# motorcontrol.net
KiCad netlist of a schematic drawn in EAGLE
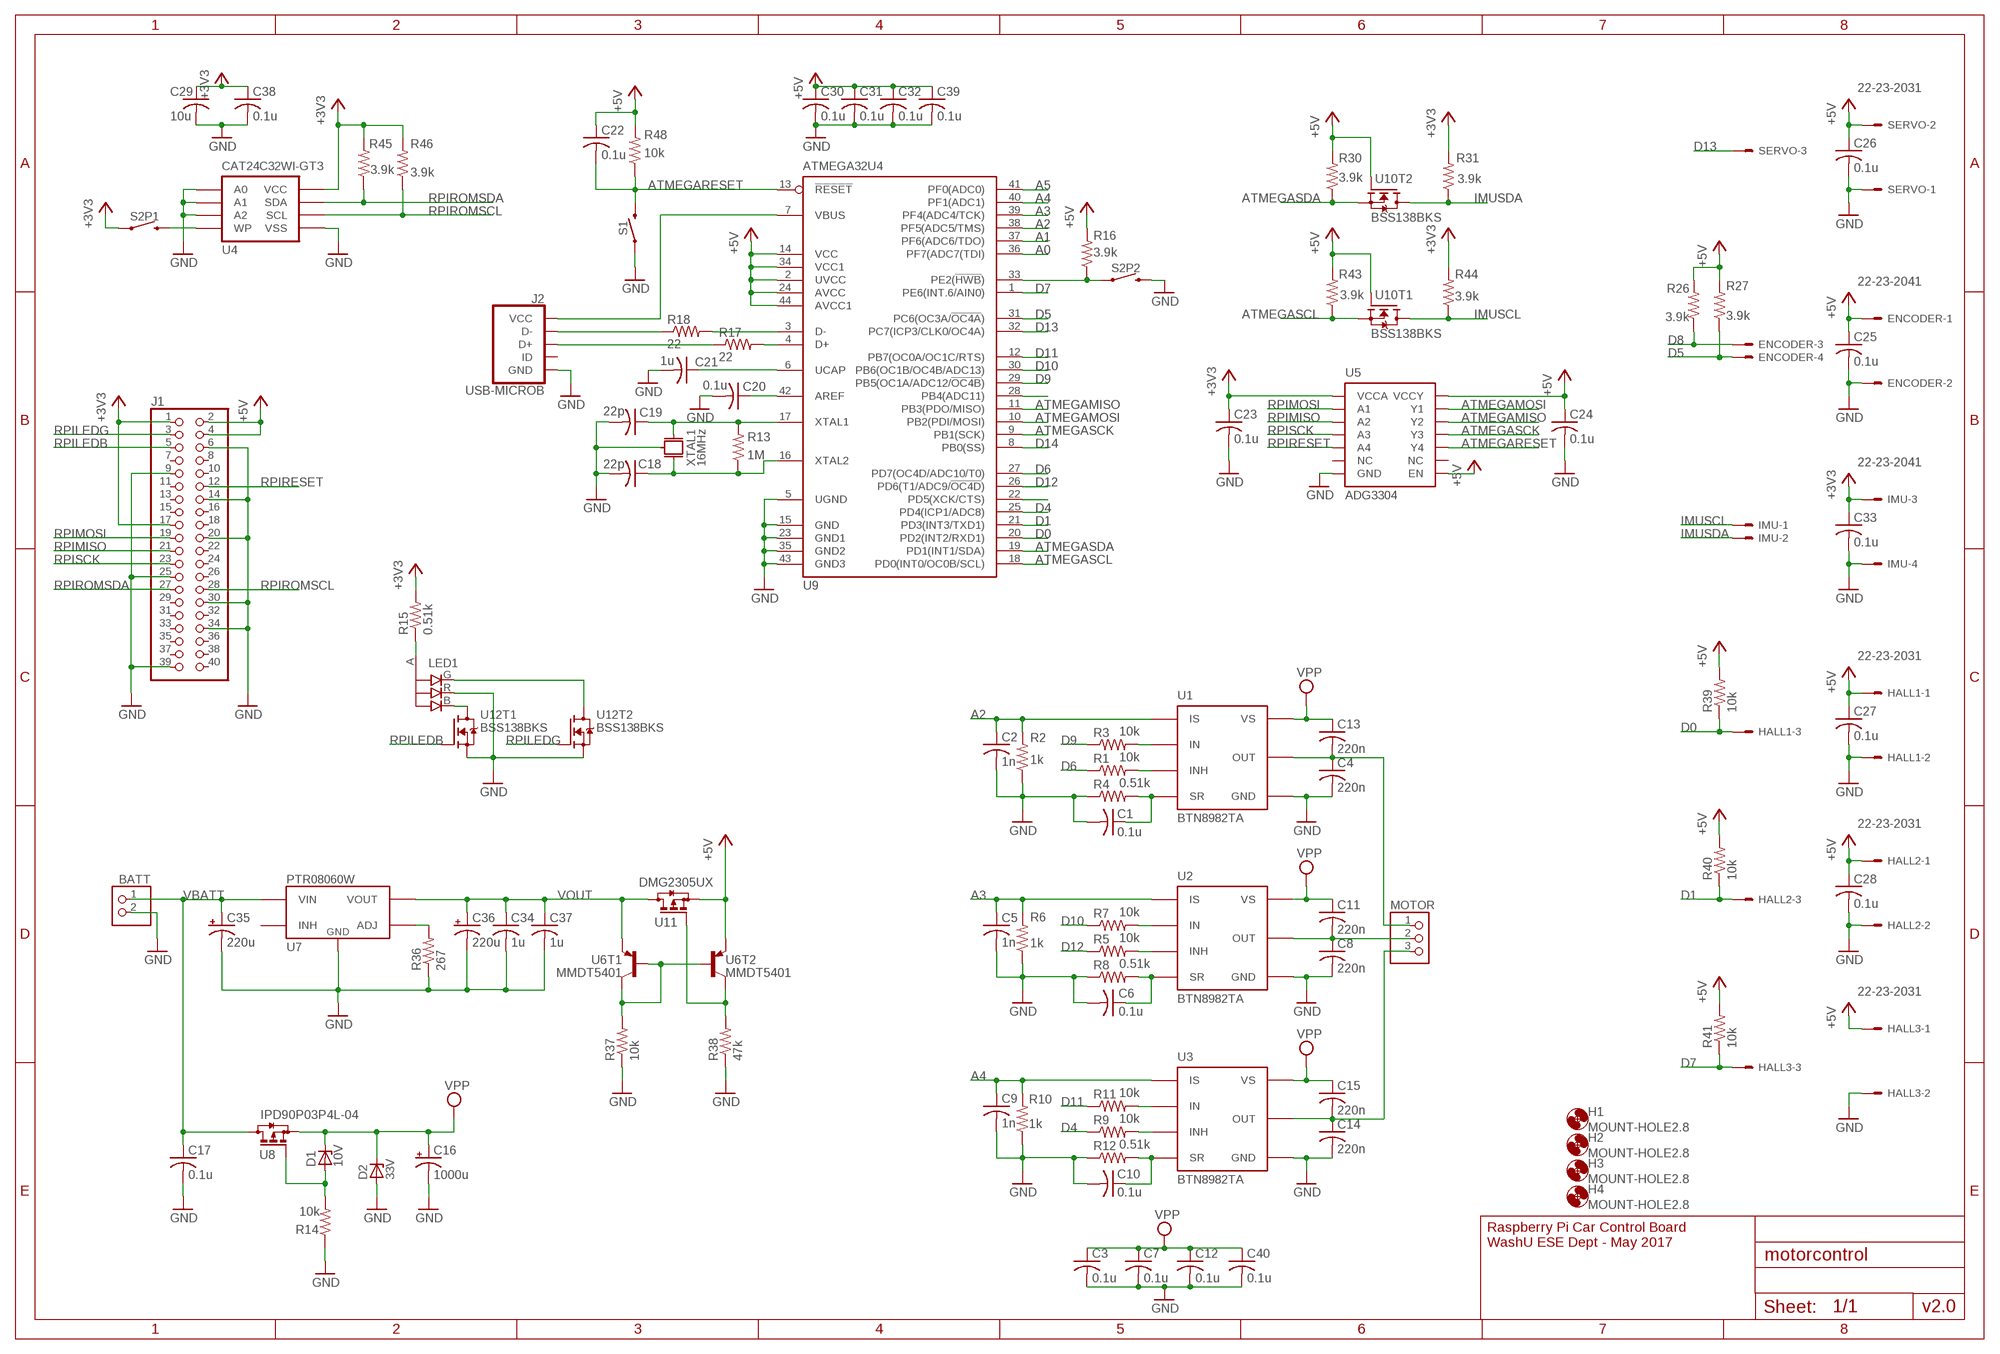
[diagram p0: schematic, sheet 1]

(export (version "E")
  (design (tool "Eeschema 10.0.6"))
  (components
    (comp (ref "BATT")
      (value "ULTRAFIT_2CIRCVCLIP")
      (footprint "eagle-import:ULTRAFIT_2CIRC_VERTCLIP")
      (libsource (lib "eagle-import") (part "ULTRAFIT_2CIRCVCLIP"))
    )
    (comp (ref "C1")
      (value "0.1u")
      (footprint "eagle-import:C1206")
      (libsource (lib "eagle-import") (part "C-USC1206"))
    )
    (comp (ref "C2")
      (value "1n")
      (footprint "eagle-import:C1206")
      (libsource (lib "eagle-import") (part "C-USC1206"))
    )
    (comp (ref "C3")
      (value "0.1u")
      (footprint "eagle-import:C1206")
      (libsource (lib "eagle-import") (part "C-USC1206"))
    )
    (comp (ref "C4")
      (value "220n")
      (footprint "eagle-import:C1206")
      (libsource (lib "eagle-import") (part "C-USC1206"))
    )
    (comp (ref "C5")
      (value "1n")
      (footprint "eagle-import:C1206")
      (libsource (lib "eagle-import") (part "C-USC1206"))
    )
    (comp (ref "C6")
      (value "0.1u")
      (footprint "eagle-import:C1206")
      (libsource (lib "eagle-import") (part "C-USC1206"))
    )
    (comp (ref "C7")
      (value "0.1u")
      (footprint "eagle-import:C1206")
      (libsource (lib "eagle-import") (part "C-USC1206"))
    )
    (comp (ref "C8")
      (value "220n")
      (footprint "eagle-import:C1206")
      (libsource (lib "eagle-import") (part "C-USC1206"))
    )
    (comp (ref "C9")
      (value "1n")
      (footprint "eagle-import:C1206")
      (libsource (lib "eagle-import") (part "C-USC1206"))
    )
    (comp (ref "C10")
      (value "0.1u")
      (footprint "eagle-import:C1206")
      (libsource (lib "eagle-import") (part "C-USC1206"))
    )
    (comp (ref "C11")
      (value "220n")
      (footprint "eagle-import:C1206")
      (libsource (lib "eagle-import") (part "C-USC1206"))
    )
    (comp (ref "C12")
      (value "0.1u")
      (footprint "eagle-import:C1206")
      (libsource (lib "eagle-import") (part "C-USC1206"))
    )
    (comp (ref "C13")
      (value "220n")
      (footprint "eagle-import:C1206")
      (libsource (lib "eagle-import") (part "C-USC1206"))
    )
    (comp (ref "C14")
      (value "220n")
      (footprint "eagle-import:C1206")
      (libsource (lib "eagle-import") (part "C-USC1206"))
    )
    (comp (ref "C15")
      (value "220n")
      (footprint "eagle-import:C1206")
      (libsource (lib "eagle-import") (part "C-USC1206"))
    )
    (comp (ref "C16")
      (value "1000u")
      (footprint "eagle-import:E5-10,5")
      (libsource (lib "eagle-import") (part "CPOL-USE5-10.5"))
    )
    (comp (ref "C17")
      (value "0.1u")
      (footprint "eagle-import:C1206")
      (libsource (lib "eagle-import") (part "C-USC1206"))
    )
    (comp (ref "C18")
      (value "22p")
      (footprint "eagle-import:C1206")
      (libsource (lib "eagle-import") (part "C-USC1206"))
    )
    (comp (ref "C19")
      (value "22p")
      (footprint "eagle-import:C1206")
      (libsource (lib "eagle-import") (part "C-USC1206"))
    )
    (comp (ref "C20")
      (value "0.1u")
      (footprint "eagle-import:C1206")
      (libsource (lib "eagle-import") (part "C-USC1206"))
    )
    (comp (ref "C21")
      (value "1u")
      (footprint "eagle-import:C1206")
      (libsource (lib "eagle-import") (part "C-USC1206"))
    )
    (comp (ref "C22")
      (value "0.1u")
      (footprint "eagle-import:C1206")
      (libsource (lib "eagle-import") (part "C-USC1206"))
    )
    (comp (ref "C23")
      (value "0.1u")
      (footprint "eagle-import:C1206")
      (libsource (lib "eagle-import") (part "C-USC1206"))
    )
    (comp (ref "C24")
      (value "0.1u")
      (footprint "eagle-import:C1206")
      (libsource (lib "eagle-import") (part "C-USC1206"))
    )
    (comp (ref "C25")
      (value "0.1u")
      (footprint "eagle-import:C1206")
      (libsource (lib "eagle-import") (part "C-USC1206"))
    )
    (comp (ref "C26")
      (value "0.1u")
      (footprint "eagle-import:C1206")
      (libsource (lib "eagle-import") (part "C-USC1206"))
    )
    (comp (ref "C27")
      (value "0.1u")
      (footprint "eagle-import:C1206")
      (libsource (lib "eagle-import") (part "C-USC1206"))
    )
    (comp (ref "C28")
      (value "0.1u")
      (footprint "eagle-import:C1206")
      (libsource (lib "eagle-import") (part "C-USC1206"))
    )
    (comp (ref "C29")
      (value "10u")
      (footprint "eagle-import:C1206")
      (libsource (lib "eagle-import") (part "C-USC1206"))
    )
    (comp (ref "C30")
      (value "0.1u")
      (footprint "eagle-import:C1206")
      (libsource (lib "eagle-import") (part "C-USC1206"))
    )
    (comp (ref "C31")
      (value "0.1u")
      (footprint "eagle-import:C1206")
      (libsource (lib "eagle-import") (part "C-USC1206"))
    )
    (comp (ref "C32")
      (value "0.1u")
      (footprint "eagle-import:C1206")
      (libsource (lib "eagle-import") (part "C-USC1206"))
    )
    (comp (ref "C33")
      (value "0.1u")
      (footprint "eagle-import:C1206")
      (libsource (lib "eagle-import") (part "C-USC1206"))
    )
    (comp (ref "C34")
      (value "1u")
      (footprint "eagle-import:C1206")
      (libsource (lib "eagle-import") (part "C-USC1206"))
    )
    (comp (ref "C35")
      (value "220u")
      (footprint "eagle-import:E3,5-8")
      (libsource (lib "eagle-import") (part "CPOL-USE3.5-8"))
    )
    (comp (ref "C36")
      (value "220u")
      (footprint "eagle-import:E3,5-8")
      (libsource (lib "eagle-import") (part "CPOL-USE3.5-8"))
    )
    (comp (ref "C37")
      (value "1u")
      (footprint "eagle-import:C1206")
      (libsource (lib "eagle-import") (part "C-USC1206"))
    )
    (comp (ref "C38")
      (value "0.1u")
      (footprint "eagle-import:C1206")
      (libsource (lib "eagle-import") (part "C-USC1206"))
    )
    (comp (ref "C39")
      (value "0.1u")
      (footprint "eagle-import:C1206")
      (libsource (lib "eagle-import") (part "C-USC1206"))
    )
    (comp (ref "C40")
      (value "0.1u")
      (footprint "eagle-import:C1206")
      (libsource (lib "eagle-import") (part "C-USC1206"))
    )
    (comp (ref "D1")
      (value "10V")
      (footprint "eagle-import:SOD80C")
      (libsource (lib "eagle-import") (part "ZENER-DIODESOD80C"))
    )
    (comp (ref "D2")
      (value "33V")
      (footprint "eagle-import:SMA")
      (libsource (lib "eagle-import") (part "SMAZX"))
    )
    (comp (ref "ENCODER")
      (value "22-23-2041")
      (footprint "eagle-import:22-23-2041")
      (fields (field (name "MF") "MOLEX"))
      (libsource (lib "eagle-import") (part "22-23-2041"))
    )
    (comp (ref "H1")
      (value "MOUNT-HOLE2.8")
      (footprint "eagle-import:2,8")
      (libsource (lib "eagle-import") (part "MOUNT-HOLE2.8"))
    )
    (comp (ref "H2")
      (value "MOUNT-HOLE2.8")
      (footprint "eagle-import:2,8")
      (libsource (lib "eagle-import") (part "MOUNT-HOLE2.8"))
    )
    (comp (ref "H3")
      (value "MOUNT-HOLE2.8")
      (footprint "eagle-import:2,8")
      (libsource (lib "eagle-import") (part "MOUNT-HOLE2.8"))
    )
    (comp (ref "H4")
      (value "MOUNT-HOLE2.8")
      (footprint "eagle-import:2,8")
      (libsource (lib "eagle-import") (part "MOUNT-HOLE2.8"))
    )
    (comp (ref "HALL1")
      (value "22-23-2031")
      (footprint "eagle-import:22-23-2031")
      (fields (field (name "MF") "MOLEX"))
      (libsource (lib "eagle-import") (part "22-23-2031"))
    )
    (comp (ref "HALL2")
      (value "22-23-2031")
      (footprint "eagle-import:22-23-2031")
      (fields (field (name "MF") "MOLEX"))
      (libsource (lib "eagle-import") (part "22-23-2031"))
    )
    (comp (ref "HALL3")
      (value "22-23-2031")
      (footprint "eagle-import:22-23-2031")
      (fields (field (name "MF") "MOLEX"))
      (libsource (lib "eagle-import") (part "22-23-2031"))
    )
    (comp (ref "IMU")
      (value "22-23-2041")
      (footprint "eagle-import:22-23-2041")
      (fields (field (name "MF") "MOLEX"))
      (libsource (lib "eagle-import") (part "22-23-2041"))
    )
    (comp (ref "J1")
      (value "RPIHEADER_2.54-SMD")
      (footprint "eagle-import:RPI_SMD")
      (libsource (lib "eagle-import") (part "RPIHEADER_2.54-SMD"))
    )
    (comp (ref "J2")
      (value "USB-MICROB")
      (footprint "eagle-import:FCI-10103594-0001LF")
      (libsource (lib "eagle-import") (part "USB-MICROB"))
    )
    (comp (ref "LED1")
      (value "MSL0201RGB")
      (footprint "eagle-import:MSL0201RGB")
      (libsource (lib "eagle-import") (part "MSL0201RGB"))
    )
    (comp (ref "MOTOR")
      (value "ULTRAFIT_3CIRCVCLIP")
      (footprint "eagle-import:ULTRAFIT_3CIRC_VERTCLIP")
      (libsource (lib "eagle-import") (part "ULTRAFIT_3CIRCVCLIP"))
    )
    (comp (ref "R1")
      (value "10k")
      (footprint "eagle-import:R1206")
      (libsource (lib "eagle-import") (part "R-US_R1206"))
    )
    (comp (ref "R2")
      (value "1k")
      (footprint "eagle-import:R1206")
      (libsource (lib "eagle-import") (part "R-US_R1206"))
    )
    (comp (ref "R3")
      (value "10k")
      (footprint "eagle-import:R1206")
      (libsource (lib "eagle-import") (part "R-US_R1206"))
    )
    (comp (ref "R4")
      (value "0.51k")
      (footprint "eagle-import:R1206")
      (libsource (lib "eagle-import") (part "R-US_R1206"))
    )
    (comp (ref "R5")
      (value "10k")
      (footprint "eagle-import:R1206")
      (libsource (lib "eagle-import") (part "R-US_R1206"))
    )
    (comp (ref "R6")
      (value "1k")
      (footprint "eagle-import:R1206")
      (libsource (lib "eagle-import") (part "R-US_R1206"))
    )
    (comp (ref "R7")
      (value "10k")
      (footprint "eagle-import:R1206")
      (libsource (lib "eagle-import") (part "R-US_R1206"))
    )
    (comp (ref "R8")
      (value "0.51k")
      (footprint "eagle-import:R1206")
      (libsource (lib "eagle-import") (part "R-US_R1206"))
    )
    (comp (ref "R9")
      (value "10k")
      (footprint "eagle-import:R1206")
      (libsource (lib "eagle-import") (part "R-US_R1206"))
    )
    (comp (ref "R10")
      (value "1k")
      (footprint "eagle-import:R1206")
      (libsource (lib "eagle-import") (part "R-US_R1206"))
    )
    (comp (ref "R11")
      (value "10k")
      (footprint "eagle-import:R1206")
      (libsource (lib "eagle-import") (part "R-US_R1206"))
    )
    (comp (ref "R12")
      (value "0.51k")
      (footprint "eagle-import:R1206")
      (libsource (lib "eagle-import") (part "R-US_R1206"))
    )
    (comp (ref "R13")
      (value "1M")
      (footprint "eagle-import:R1206")
      (libsource (lib "eagle-import") (part "R-US_R1206"))
    )
    (comp (ref "R14")
      (value "10k")
      (footprint "eagle-import:R1206")
      (libsource (lib "eagle-import") (part "R-US_R1206"))
    )
    (comp (ref "R15")
      (value "0.51k")
      (footprint "eagle-import:R1206")
      (libsource (lib "eagle-import") (part "R-US_R1206"))
    )
    (comp (ref "R16")
      (value "3.9k")
      (footprint "eagle-import:R1206")
      (libsource (lib "eagle-import") (part "R-US_R1206"))
    )
    (comp (ref "R17")
      (value "22")
      (footprint "eagle-import:R1206")
      (libsource (lib "eagle-import") (part "R-US_R1206"))
    )
    (comp (ref "R18")
      (value "22")
      (footprint "eagle-import:R1206")
      (libsource (lib "eagle-import") (part "R-US_R1206"))
    )
    (comp (ref "R26")
      (value "3.9k")
      (footprint "eagle-import:R1206")
      (libsource (lib "eagle-import") (part "R-US_R1206"))
    )
    (comp (ref "R27")
      (value "3.9k")
      (footprint "eagle-import:R1206")
      (libsource (lib "eagle-import") (part "R-US_R1206"))
    )
    (comp (ref "R30")
      (value "3.9k")
      (footprint "eagle-import:R1206")
      (libsource (lib "eagle-import") (part "R-US_R1206"))
    )
    (comp (ref "R31")
      (value "3.9k")
      (footprint "eagle-import:R1206")
      (libsource (lib "eagle-import") (part "R-US_R1206"))
    )
    (comp (ref "R36")
      (value "267")
      (footprint "eagle-import:R1206")
      (libsource (lib "eagle-import") (part "R-US_R1206"))
    )
    (comp (ref "R37")
      (value "10k")
      (footprint "eagle-import:R1206")
      (libsource (lib "eagle-import") (part "R-US_R1206"))
    )
    (comp (ref "R38")
      (value "47k")
      (footprint "eagle-import:R1206")
      (libsource (lib "eagle-import") (part "R-US_R1206"))
    )
    (comp (ref "R39")
      (value "10k")
      (footprint "eagle-import:R1206")
      (libsource (lib "eagle-import") (part "R-US_R1206"))
    )
    (comp (ref "R40")
      (value "10k")
      (footprint "eagle-import:R1206")
      (libsource (lib "eagle-import") (part "R-US_R1206"))
    )
    (comp (ref "R41")
      (value "10k")
      (footprint "eagle-import:R1206")
      (libsource (lib "eagle-import") (part "R-US_R1206"))
    )
    (comp (ref "R43")
      (value "3.9k")
      (footprint "eagle-import:R1206")
      (libsource (lib "eagle-import") (part "R-US_R1206"))
    )
    (comp (ref "R44")
      (value "3.9k")
      (footprint "eagle-import:R1206")
      (libsource (lib "eagle-import") (part "R-US_R1206"))
    )
    (comp (ref "R45")
      (value "3.9k")
      (footprint "eagle-import:R1206")
      (libsource (lib "eagle-import") (part "R-US_R1206"))
    )
    (comp (ref "R46")
      (value "3.9k")
      (footprint "eagle-import:R1206")
      (libsource (lib "eagle-import") (part "R-US_R1206"))
    )
    (comp (ref "R48")
      (value "10k")
      (footprint "eagle-import:R1206")
      (libsource (lib "eagle-import") (part "R-US_R1206"))
    )
    (comp (ref "S1")
      (value "B3U-3000P-B")
      (footprint "eagle-import:B3U-3000P-B")
      (libsource (lib "eagle-import") (part "B3U-3000P-B"))
    )
    (comp (ref "S2")
      (value "A6HF-2DIP")
      (footprint "eagle-import:A6HF")
      (libsource (lib "eagle-import") (part "A6HF-2DIP"))
    )
    (comp (ref "SERVO")
      (value "22-23-2031")
      (footprint "eagle-import:22-23-2031")
      (fields (field (name "MF") "MOLEX"))
      (libsource (lib "eagle-import") (part "22-23-2031"))
    )
    (comp (ref "U1")
      (value "BTN8982TA")
      (footprint "eagle-import:TO263-7")
      (libsource (lib "eagle-import") (part "BTN8982TA"))
    )
    (comp (ref "U2")
      (value "BTN8982TA")
      (footprint "eagle-import:TO263-7")
      (libsource (lib "eagle-import") (part "BTN8982TA"))
    )
    (comp (ref "U3")
      (value "BTN8982TA")
      (footprint "eagle-import:TO263-7")
      (libsource (lib "eagle-import") (part "BTN8982TA"))
    )
    (comp (ref "U4")
      (value "CAT24C32WI-GT3")
      (footprint "eagle-import:SOIC8")
      (libsource (lib "eagle-import") (part "CAT24C32WI-GT3"))
    )
    (comp (ref "U5")
      (value "ADG3304")
      (footprint "eagle-import:TSSOP14")
      (libsource (lib "eagle-import") (part "ADG3304"))
    )
    (comp (ref "U6")
      (value "MMDT5401")
      (footprint "eagle-import:SOT363")
      (libsource (lib "eagle-import") (part "MMDT5401"))
    )
    (comp (ref "U7")
      (value "PTR08060W")
      (footprint "eagle-import:EDP_MODULE")
      (libsource (lib "eagle-import") (part "PTR08060W"))
    )
    (comp (ref "U8")
      (value "IPD90P03P4L-04")
      (footprint "eagle-import:TO252-3-11")
      (libsource (lib "eagle-import") (part "IPD90P03P4L-04"))
    )
    (comp (ref "U9")
      (value "ATMEGA32U4")
      (footprint "eagle-import:TQFP44")
      (libsource (lib "eagle-import") (part "ATMEGA32U4"))
    )
    (comp (ref "U10")
      (value "BSS138BKS")
      (footprint "eagle-import:SOT363")
      (libsource (lib "eagle-import") (part "BSS138BKS"))
    )
    (comp (ref "U11")
      (value "DMG2305UX")
      (footprint "eagle-import:SOT23-3")
      (libsource (lib "eagle-import") (part "DMG2305UX"))
    )
    (comp (ref "U12")
      (value "BSS138BKS")
      (footprint "eagle-import:SOT363")
      (libsource (lib "eagle-import") (part "BSS138BKS"))
    )
    (comp (ref "XTAL1")
      (value "16MHz")
      (footprint "eagle-import:ABM3B")
      (libsource (lib "eagle-import") (part "CRYSTAL"))
    )
  )
  (nets
    (net (code "1") (name "+3V3") (class "Default")
      (node (ref "C23") (pin "1") (pinfunction "1_1") (pintype "passive"))
      (node (ref "C29") (pin "1") (pinfunction "1_1") (pintype "passive"))
      (node (ref "C33") (pin "1") (pinfunction "1_1") (pintype "passive"))
      (node (ref "C38") (pin "1") (pinfunction "1_1") (pintype "passive"))
      (node (ref "IMU") (pin "3") (pinfunction "S_3") (pintype "passive"))
      (node (ref "J1") (pin "1") (pinfunction "1_1") (pintype "passive"))
      (node (ref "J1") (pin "17") (pinfunction "17_17") (pintype "passive"))
      (node (ref "R15") (pin "2") (pinfunction "2_2") (pintype "passive"))
      (node (ref "R31") (pin "2") (pinfunction "2_2") (pintype "passive"))
      (node (ref "R44") (pin "2") (pinfunction "2_2") (pintype "passive"))
      (node (ref "R45") (pin "2") (pinfunction "2_2") (pintype "passive"))
      (node (ref "R46") (pin "2") (pinfunction "2_2") (pintype "passive"))
      (node (ref "S2") (pin "P1.1") (pinfunction "1_P1.1") (pintype "passive"))
      (node (ref "U4") (pin "8") (pinfunction "VCC_8") (pintype "power_in"))
      (node (ref "U5") (pin "1") (pinfunction "VCCA_1") (pintype "power_in"))
    )
    (net (code "2") (name "+5V") (class "Default")
      (node (ref "C22") (pin "1") (pinfunction "1_1") (pintype "passive"))
      (node (ref "C24") (pin "1") (pinfunction "1_1") (pintype "passive"))
      (node (ref "C25") (pin "1") (pinfunction "1_1") (pintype "passive"))
      (node (ref "C26") (pin "1") (pinfunction "1_1") (pintype "passive"))
      (node (ref "C27") (pin "1") (pinfunction "1_1") (pintype "passive"))
      (node (ref "C28") (pin "1") (pinfunction "1_1") (pintype "passive"))
      (node (ref "C30") (pin "1") (pinfunction "1_1") (pintype "passive"))
      (node (ref "C31") (pin "1") (pinfunction "1_1") (pintype "passive"))
      (node (ref "C32") (pin "1") (pinfunction "1_1") (pintype "passive"))
      (node (ref "C39") (pin "1") (pinfunction "1_1") (pintype "passive"))
      (node (ref "ENCODER") (pin "1") (pinfunction "S_1") (pintype "passive"))
      (node (ref "HALL1") (pin "1") (pinfunction "S_1") (pintype "passive"))
      (node (ref "HALL2") (pin "1") (pinfunction "S_1") (pintype "passive"))
      (node (ref "HALL3") (pin "1") (pinfunction "S_1") (pintype "passive"))
      (node (ref "J1") (pin "2") (pinfunction "2_2") (pintype "passive"))
      (node (ref "J1") (pin "4") (pinfunction "4_4") (pintype "passive"))
      (node (ref "R16") (pin "2") (pinfunction "2_2") (pintype "passive"))
      (node (ref "R26") (pin "2") (pinfunction "2_2") (pintype "passive"))
      (node (ref "R27") (pin "2") (pinfunction "2_2") (pintype "passive"))
      (node (ref "R30") (pin "2") (pinfunction "2_2") (pintype "passive"))
      (node (ref "R39") (pin "2") (pinfunction "2_2") (pintype "passive"))
      (node (ref "R40") (pin "2") (pinfunction "2_2") (pintype "passive"))
      (node (ref "R41") (pin "2") (pinfunction "2_2") (pintype "passive"))
      (node (ref "R43") (pin "2") (pinfunction "2_2") (pintype "passive"))
      (node (ref "R48") (pin "2") (pinfunction "2_2") (pintype "passive"))
      (node (ref "SERVO") (pin "2") (pinfunction "S_2") (pintype "passive"))
      (node (ref "U10") (pin "2") (pinfunction "G_2") (pintype "passive"))
      (node (ref "U10") (pin "5") (pinfunction "G_5") (pintype "passive"))
      (node (ref "U11") (pin "2") (pinfunction "S_2") (pintype "passive"))
      (node (ref "U5") (pin "14") (pinfunction "VCCY_14") (pintype "power_in"))
      (node (ref "U5") (pin "8") (pinfunction "EN_8") (pintype "input"))
      (node (ref "U6") (pin "4") (pinfunction "E_4") (pintype "passive"))
      (node (ref "U9") (pin "14") (pinfunction "VCC_14") (pintype "bidirectional"))
      (node (ref "U9") (pin "2") (pinfunction "UVCC_2") (pintype "bidirectional"))
      (node (ref "U9") (pin "24") (pinfunction "AVCC_24") (pintype "bidirectional"))
      (node (ref "U9") (pin "34") (pinfunction "VCC1_34") (pintype "bidirectional"))
      (node (ref "U9") (pin "44") (pinfunction "AVCC1_44") (pintype "bidirectional"))
    )
    (net (code "3") (name "/A0") (class "Default")
      (node (ref "U9") (pin "36") (pinfunction "PF7(ADC7(TDI)_36") (pintype "bidirectional"))
    )
    (net (code "4") (name "/A1") (class "Default")
      (node (ref "U9") (pin "37") (pinfunction "PF6(ADC6/TDO)_37") (pintype "bidirectional"))
    )
    (net (code "5") (name "/A2") (class "Default")
      (node (ref "C2") (pin "1") (pinfunction "1_1") (pintype "passive"))
      (node (ref "R2") (pin "2") (pinfunction "2_2") (pintype "passive"))
      (node (ref "U1") (pin "6") (pinfunction "IS_6") (pintype "output"))
      (node (ref "U9") (pin "38") (pinfunction "PF5(ADC5/TMS)_38") (pintype "bidirectional"))
    )
    (net (code "6") (name "/A3") (class "Default")
      (node (ref "C5") (pin "1") (pinfunction "1_1") (pintype "passive"))
      (node (ref "R6") (pin "2") (pinfunction "2_2") (pintype "passive"))
      (node (ref "U2") (pin "6") (pinfunction "IS_6") (pintype "output"))
      (node (ref "U9") (pin "39") (pinfunction "PF4(ADC4/TCK)_39") (pintype "bidirectional"))
    )
    (net (code "7") (name "/A4") (class "Default")
      (node (ref "C9") (pin "1") (pinfunction "1_1") (pintype "passive"))
      (node (ref "R10") (pin "2") (pinfunction "2_2") (pintype "passive"))
      (node (ref "U3") (pin "6") (pinfunction "IS_6") (pintype "output"))
      (node (ref "U9") (pin "40") (pinfunction "PF1(ADC1)_40") (pintype "bidirectional"))
    )
    (net (code "8") (name "/A5") (class "Default")
      (node (ref "U9") (pin "41") (pinfunction "PF0(ADC0)_41") (pintype "bidirectional"))
    )
    (net (code "9") (name "/ATMEGAMISO") (class "Default")
      (node (ref "U5") (pin "12") (pinfunction "Y2_12") (pintype "bidirectional"))
      (node (ref "U9") (pin "11") (pinfunction "PB3(PDO/MISO)_11") (pintype "bidirectional"))
    )
    (net (code "10") (name "/ATMEGAMOSI") (class "Default")
      (node (ref "U5") (pin "13") (pinfunction "Y1_13") (pintype "bidirectional"))
      (node (ref "U9") (pin "10") (pinfunction "PB2(PDI/MOSI)_10") (pintype "bidirectional"))
    )
    (net (code "11") (name "/ATMEGARESET") (class "Default")
      (node (ref "C22") (pin "2") (pinfunction "2_2") (pintype "passive"))
      (node (ref "R48") (pin "1") (pinfunction "1_1") (pintype "passive"))
      (node (ref "S1") (pin "2") (pinfunction "2_2") (pintype "passive"))
      (node (ref "U5") (pin "10") (pinfunction "Y4_10") (pintype "bidirectional"))
      (node (ref "U9") (pin "13") (pinfunction "~{RESET}_13") (pintype "bidirectional"))
    )
    (net (code "12") (name "/ATMEGASCK") (class "Default")
      (node (ref "U5") (pin "11") (pinfunction "Y3_11") (pintype "bidirectional"))
      (node (ref "U9") (pin "9") (pinfunction "PB1(SCK)_9") (pintype "bidirectional"))
    )
    (net (code "13") (name "/ATMEGASCL") (class "Default")
      (node (ref "R43") (pin "1") (pinfunction "1_1") (pintype "passive"))
      (node (ref "U10") (pin "1") (pinfunction "S_1") (pintype "passive"))
      (node (ref "U9") (pin "18") (pinfunction "PD0(INT0/OC0B/SCL)_18") (pintype "bidirectional"))
    )
    (net (code "14") (name "/ATMEGASDA") (class "Default")
      (node (ref "R30") (pin "1") (pinfunction "1_1") (pintype "passive"))
      (node (ref "U10") (pin "4") (pinfunction "S_4") (pintype "passive"))
      (node (ref "U9") (pin "19") (pinfunction "PD1(INT1/SDA)_19") (pintype "bidirectional"))
    )
    (net (code "15") (name "/D0") (class "Default")
      (node (ref "HALL1") (pin "3") (pinfunction "S_3") (pintype "passive"))
      (node (ref "R39") (pin "1") (pinfunction "1_1") (pintype "passive"))
      (node (ref "U9") (pin "20") (pinfunction "PD2(INT2/RXD1)_20") (pintype "bidirectional"))
    )
    (net (code "16") (name "/D1") (class "Default")
      (node (ref "HALL2") (pin "3") (pinfunction "S_3") (pintype "passive"))
      (node (ref "R40") (pin "1") (pinfunction "1_1") (pintype "passive"))
      (node (ref "U9") (pin "21") (pinfunction "PD3(INT3/TXD1)_21") (pintype "bidirectional"))
    )
    (net (code "17") (name "/D4") (class "Default")
      (node (ref "R9") (pin "1") (pinfunction "1_1") (pintype "passive"))
      (node (ref "U9") (pin "25") (pinfunction "PD4(ICP1/ADC8)_25") (pintype "bidirectional"))
    )
    (net (code "18") (name "/D5") (class "Default")
      (node (ref "ENCODER") (pin "4") (pinfunction "S_4") (pintype "passive"))
      (node (ref "R27") (pin "1") (pinfunction "1_1") (pintype "passive"))
      (node (ref "U9") (pin "31") (pinfunction "PC6(OC3A/~{OC4A})_31") (pintype "bidirectional"))
    )
    (net (code "19") (name "/D6") (class "Default")
      (node (ref "R1") (pin "1") (pinfunction "1_1") (pintype "passive"))
      (node (ref "U9") (pin "27") (pinfunction "PD7(OC4D/ADC10/T0)_27") (pintype "bidirectional"))
    )
    (net (code "20") (name "/D7") (class "Default")
      (node (ref "HALL3") (pin "3") (pinfunction "S_3") (pintype "passive"))
      (node (ref "R41") (pin "1") (pinfunction "1_1") (pintype "passive"))
      (node (ref "U9") (pin "1") (pinfunction "PE6(INT.6/AIN0)_1") (pintype "bidirectional"))
    )
    (net (code "21") (name "/D8") (class "Default")
      (node (ref "ENCODER") (pin "3") (pinfunction "S_3") (pintype "passive"))
      (node (ref "R26") (pin "1") (pinfunction "1_1") (pintype "passive"))
      (node (ref "U9") (pin "28") (pinfunction "PB4(ADC11)_28") (pintype "bidirectional"))
    )
    (net (code "22") (name "/D9") (class "Default")
      (node (ref "R3") (pin "1") (pinfunction "1_1") (pintype "passive"))
      (node (ref "U9") (pin "29") (pinfunction "PB5(OC1A/ADC12/~{OC4B})_29") (pintype "bidirectional"))
    )
    (net (code "23") (name "/D10") (class "Default")
      (node (ref "R7") (pin "1") (pinfunction "1_1") (pintype "passive"))
      (node (ref "U9") (pin "30") (pinfunction "PB6(OC1B/OC4B/ADC13)_30") (pintype "bidirectional"))
    )
    (net (code "24") (name "/D11") (class "Default")
      (node (ref "R11") (pin "1") (pinfunction "1_1") (pintype "passive"))
      (node (ref "U9") (pin "12") (pinfunction "PB7(OC0A/OC1C/RTS)_12") (pintype "bidirectional"))
    )
    (net (code "25") (name "/D12") (class "Default")
      (node (ref "R5") (pin "1") (pinfunction "1_1") (pintype "passive"))
      (node (ref "U9") (pin "26") (pinfunction "PD6(T1/ADC9/~{OC4D})_26") (pintype "bidirectional"))
    )
    (net (code "26") (name "/D13") (class "Default")
      (node (ref "SERVO") (pin "3") (pinfunction "S_3") (pintype "passive"))
      (node (ref "U9") (pin "32") (pinfunction "PC7(ICP3/CLK0/OC4A)_32") (pintype "bidirectional"))
    )
    (net (code "27") (name "/D14") (class "Default")
      (node (ref "U9") (pin "8") (pinfunction "PB0(SS)_8") (pintype "bidirectional"))
    )
    (net (code "28") (name "/IMUSCL") (class "Default")
      (node (ref "IMU") (pin "1") (pinfunction "S_1") (pintype "passive"))
      (node (ref "R44") (pin "1") (pinfunction "1_1") (pintype "passive"))
      (node (ref "U10") (pin "6") (pinfunction "D_6") (pintype "passive"))
    )
    (net (code "29") (name "/IMUSDA") (class "Default")
      (node (ref "IMU") (pin "2") (pinfunction "S_2") (pintype "passive"))
      (node (ref "R31") (pin "1") (pinfunction "1_1") (pintype "passive"))
      (node (ref "U10") (pin "3") (pinfunction "D_3") (pintype "passive"))
    )
    (net (code "30") (name "/RPILEDB") (class "Default")
      (node (ref "J1") (pin "5") (pinfunction "5_5") (pintype "passive"))
      (node (ref "U12") (pin "2") (pinfunction "G_2") (pintype "passive"))
    )
    (net (code "31") (name "/RPILEDG") (class "Default")
      (node (ref "J1") (pin "3") (pinfunction "3_3") (pintype "passive"))
      (node (ref "U12") (pin "5") (pinfunction "G_5") (pintype "passive"))
    )
    (net (code "32") (name "/RPIMISO") (class "Default")
      (node (ref "J1") (pin "21") (pinfunction "21_21") (pintype "passive"))
      (node (ref "U5") (pin "3") (pinfunction "A2_3") (pintype "bidirectional"))
    )
    (net (code "33") (name "/RPIMOSI") (class "Default")
      (node (ref "J1") (pin "19") (pinfunction "19_19") (pintype "passive"))
      (node (ref "U5") (pin "2") (pinfunction "A1_2") (pintype "bidirectional"))
    )
    (net (code "34") (name "/RPIRESET") (class "Default")
      (node (ref "J1") (pin "12") (pinfunction "12_12") (pintype "passive"))
      (node (ref "U5") (pin "5") (pinfunction "A4_5") (pintype "bidirectional"))
    )
    (net (code "35") (name "/RPIROMSCL") (class "Default")
      (node (ref "J1") (pin "28") (pinfunction "28_28") (pintype "passive"))
      (node (ref "R46") (pin "1") (pinfunction "1_1") (pintype "passive"))
      (node (ref "U4") (pin "6") (pinfunction "SCL_6") (pintype "input"))
    )
    (net (code "36") (name "/RPIROMSDA") (class "Default")
      (node (ref "J1") (pin "27") (pinfunction "27_27") (pintype "passive"))
      (node (ref "R45") (pin "1") (pinfunction "1_1") (pintype "passive"))
      (node (ref "U4") (pin "5") (pinfunction "SDA_5") (pintype "bidirectional"))
    )
    (net (code "37") (name "/RPISCK") (class "Default")
      (node (ref "J1") (pin "23") (pinfunction "23_23") (pintype "passive"))
      (node (ref "U5") (pin "4") (pinfunction "A3_4") (pintype "bidirectional"))
    )
    (net (code "38") (name "/VBATT") (class "Default")
      (node (ref "BATT") (pin "1") (pinfunction "P1_1") (pintype "passive"))
      (node (ref "C17") (pin "1") (pinfunction "1_1") (pintype "passive"))
      (node (ref "C35") (pin "+") (pinfunction "+_+") (pintype "passive"))
      (node (ref "U7") (pin "P2") (pinfunction "VIN_P2") (pintype "power_in"))
      (node (ref "U8") (pin "2") (pinfunction "D_2") (pintype "passive"))
    )
    (net (code "39") (name "/VOUT") (class "Default")
      (node (ref "C34") (pin "1") (pinfunction "1_1") (pintype "passive"))
      (node (ref "C36") (pin "+") (pinfunction "+_+") (pintype "passive"))
      (node (ref "C37") (pin "1") (pinfunction "1_1") (pintype "passive"))
      (node (ref "U11") (pin "3") (pinfunction "D_3") (pintype "passive"))
      (node (ref "U6") (pin "1") (pinfunction "E_1") (pintype "passive"))
      (node (ref "U7") (pin "P4") (pinfunction "VOUT_P4") (pintype "power_in"))
    )
    (net (code "40") (name "GND") (class "Default")
      (node (ref "BATT") (pin "2") (pinfunction "P2_2") (pintype "passive"))
      (node (ref "C1") (pin "2") (pinfunction "2_2") (pintype "passive"))
      (node (ref "C10") (pin "2") (pinfunction "2_2") (pintype "passive"))
      (node (ref "C12") (pin "2") (pinfunction "2_2") (pintype "passive"))
      (node (ref "C14") (pin "2") (pinfunction "2_2") (pintype "passive"))
      (node (ref "C16") (pin "-") (pinfunction "-_-") (pintype "passive"))
      (node (ref "C17") (pin "2") (pinfunction "2_2") (pintype "passive"))
      (node (ref "C18") (pin "2") (pinfunction "2_2") (pintype "passive"))
      (node (ref "C19") (pin "2") (pinfunction "2_2") (pintype "passive"))
      (node (ref "C2") (pin "2") (pinfunction "2_2") (pintype "passive"))
      (node (ref "C20") (pin "2") (pinfunction "2_2") (pintype "passive"))
      (node (ref "C21") (pin "2") (pinfunction "2_2") (pintype "passive"))
      (node (ref "C23") (pin "2") (pinfunction "2_2") (pintype "passive"))
      (node (ref "C24") (pin "2") (pinfunction "2_2") (pintype "passive"))
      (node (ref "C25") (pin "2") (pinfunction "2_2") (pintype "passive"))
      (node (ref "C26") (pin "2") (pinfunction "2_2") (pintype "passive"))
      (node (ref "C27") (pin "2") (pinfunction "2_2") (pintype "passive"))
      (node (ref "C28") (pin "2") (pinfunction "2_2") (pintype "passive"))
      (node (ref "C29") (pin "2") (pinfunction "2_2") (pintype "passive"))
      (node (ref "C3") (pin "2") (pinfunction "2_2") (pintype "passive"))
      (node (ref "C30") (pin "2") (pinfunction "2_2") (pintype "passive"))
      (node (ref "C31") (pin "2") (pinfunction "2_2") (pintype "passive"))
      (node (ref "C32") (pin "2") (pinfunction "2_2") (pintype "passive"))
      (node (ref "C33") (pin "2") (pinfunction "2_2") (pintype "passive"))
      (node (ref "C34") (pin "2") (pinfunction "2_2") (pintype "passive"))
      (node (ref "C35") (pin "-") (pinfunction "-_-") (pintype "passive"))
      (node (ref "C36") (pin "-") (pinfunction "-_-") (pintype "passive"))
      (node (ref "C37") (pin "2") (pinfunction "2_2") (pintype "passive"))
      (node (ref "C38") (pin "2") (pinfunction "2_2") (pintype "passive"))
      (node (ref "C39") (pin "2") (pinfunction "2_2") (pintype "passive"))
      (node (ref "C4") (pin "2") (pinfunction "2_2") (pintype "passive"))
      (node (ref "C40") (pin "2") (pinfunction "2_2") (pintype "passive"))
      (node (ref "C5") (pin "2") (pinfunction "2_2") (pintype "passive"))
      (node (ref "C6") (pin "2") (pinfunction "2_2") (pintype "passive"))
      (node (ref "C7") (pin "2") (pinfunction "2_2") (pintype "passive"))
      (node (ref "C8") (pin "2") (pinfunction "2_2") (pintype "passive"))
      (node (ref "C9") (pin "2") (pinfunction "2_2") (pintype "passive"))
      (node (ref "D2") (pin "A") (pinfunction "A_A") (pintype "passive"))
      (node (ref "ENCODER") (pin "2") (pinfunction "S_2") (pintype "passive"))
      (node (ref "HALL1") (pin "2") (pinfunction "S_2") (pintype "passive"))
      (node (ref "HALL2") (pin "2") (pinfunction "S_2") (pintype "passive"))
      (node (ref "HALL3") (pin "2") (pinfunction "S_2") (pintype "passive"))
      (node (ref "IMU") (pin "4") (pinfunction "S_4") (pintype "passive"))
      (node (ref "J1") (pin "14") (pinfunction "14_14") (pintype "passive"))
      (node (ref "J1") (pin "20") (pinfunction "20_20") (pintype "passive"))
      (node (ref "J1") (pin "25") (pinfunction "25_25") (pintype "passive"))
      (node (ref "J1") (pin "30") (pinfunction "30_30") (pintype "passive"))
      (node (ref "J1") (pin "34") (pinfunction "34_34") (pintype "passive"))
      (node (ref "J1") (pin "39") (pinfunction "39_39") (pintype "passive"))
      (node (ref "J1") (pin "6") (pinfunction "6_6") (pintype "passive"))
      (node (ref "J1") (pin "9") (pinfunction "9_9") (pintype "passive"))
      (node (ref "J2") (pin "5") (pinfunction "GND_5") (pintype "passive"))
      (node (ref "J2") (pin "GND1") (pinfunction "GND_GND1") (pintype "passive"))
      (node (ref "J2") (pin "GND2") (pinfunction "GND_GND2") (pintype "passive"))
      (node (ref "LED1") (pin "R") (pinfunction "R_R") (pintype "passive"))
      (node (ref "R10") (pin "1") (pinfunction "1_1") (pintype "passive"))
      (node (ref "R12") (pin "1") (pinfunction "1_1") (pintype "passive"))
      (node (ref "R14") (pin "1") (pinfunction "1_1") (pintype "passive"))
      (node (ref "R2") (pin "1") (pinfunction "1_1") (pintype "passive"))
      (node (ref "R36") (pin "1") (pinfunction "1_1") (pintype "passive"))
      (node (ref "R37") (pin "1") (pinfunction "1_1") (pintype "passive"))
      (node (ref "R38") (pin "1") (pinfunction "1_1") (pintype "passive"))
      (node (ref "R4") (pin "1") (pinfunction "1_1") (pintype "passive"))
      (node (ref "R6") (pin "1") (pinfunction "1_1") (pintype "passive"))
      (node (ref "R8") (pin "1") (pinfunction "1_1") (pintype "passive"))
      (node (ref "S1") (pin "1") (pinfunction "1_1") (pintype "passive"))
      (node (ref "S2") (pin "P2.2") (pinfunction "2_P2.2") (pintype "passive"))
      (node (ref "SERVO") (pin "1") (pinfunction "S_1") (pintype "passive"))
      (node (ref "U1") (pin "1") (pinfunction "GND_1") (pintype "power_in"))
      (node (ref "U12") (pin "1") (pinfunction "S_1") (pintype "passive"))
      (node (ref "U12") (pin "4") (pinfunction "S_4") (pintype "passive"))
      (node (ref "U2") (pin "1") (pinfunction "GND_1") (pintype "power_in"))
      (node (ref "U3") (pin "1") (pinfunction "GND_1") (pintype "power_in"))
      (node (ref "U4") (pin "1") (pinfunction "A0_1") (pintype "input"))
      (node (ref "U4") (pin "2") (pinfunction "A1_2") (pintype "input"))
      (node (ref "U4") (pin "3") (pinfunction "A2_3") (pintype "input"))
      (node (ref "U4") (pin "4") (pinfunction "VSS_4") (pintype "passive"))
      (node (ref "U5") (pin "7") (pinfunction "GND_7") (pintype "power_in"))
      (node (ref "U7") (pin "P3") (pinfunction "GND_P3") (pintype "power_in"))
      (node (ref "U9") (pin "15") (pinfunction "GND_15") (pintype "bidirectional"))
      (node (ref "U9") (pin "23") (pinfunction "GND1_23") (pintype "bidirectional"))
      (node (ref "U9") (pin "35") (pinfunction "GND2_35") (pintype "bidirectional"))
      (node (ref "U9") (pin "43") (pinfunction "GND3_43") (pintype "bidirectional"))
      (node (ref "U9") (pin "5") (pinfunction "UGND_5") (pintype "bidirectional"))
      (node (ref "XTAL1") (pin "GND2") (pinfunction "2_GND2") (pintype "passive"))
      (node (ref "XTAL1") (pin "GND4") (pinfunction "2_GND4") (pintype "passive"))
    )
    (net (code "41") (name "Net-(J2-D+)") (class "Default")
      (node (ref "J2") (pin "3") (pinfunction "D+_3") (pintype "bidirectional"))
      (node (ref "R17") (pin "1") (pinfunction "1_1") (pintype "passive"))
    )
    (net (code "42") (name "Net-(J2-D-)") (class "Default")
      (node (ref "J2") (pin "2") (pinfunction "D-_2") (pintype "bidirectional"))
      (node (ref "R18") (pin "1") (pinfunction "1_1") (pintype "passive"))
    )
    (net (code "43") (name "Net-(J2-VCC)") (class "Default")
      (node (ref "J2") (pin "1") (pinfunction "VCC_1") (pintype "power_in"))
      (node (ref "U9") (pin "7") (pinfunction "VBUS_7") (pintype "bidirectional"))
    )
    (net (code "44") (name "Net-(LED1-PadA)") (class "Default")
      (node (ref "LED1") (pin "A") (pinfunction "A_A") (pintype "passive"))
      (node (ref "R15") (pin "1") (pinfunction "1_1") (pintype "passive"))
    )
    (net (code "45") (name "Net-(MOTOR-P1)") (class "Default")
      (node (ref "C13") (pin "2") (pinfunction "2_2") (pintype "passive"))
      (node (ref "C4") (pin "1") (pinfunction "1_1") (pintype "passive"))
      (node (ref "MOTOR") (pin "1") (pinfunction "P1_1") (pintype "passive"))
      (node (ref "U1") (pin "4") (pinfunction "OUT_4") (pintype "passive"))
      (node (ref "U1") (pin "8") (pinfunction "OUT_8") (pintype "passive"))
    )
    (net (code "46") (name "Net-(MOTOR-P2)") (class "Default")
      (node (ref "C11") (pin "2") (pinfunction "2_2") (pintype "passive"))
      (node (ref "C8") (pin "1") (pinfunction "1_1") (pintype "passive"))
      (node (ref "MOTOR") (pin "2") (pinfunction "P2_2") (pintype "passive"))
      (node (ref "U2") (pin "4") (pinfunction "OUT_4") (pintype "passive"))
      (node (ref "U2") (pin "8") (pinfunction "OUT_8") (pintype "passive"))
    )
    (net (code "47") (name "Net-(MOTOR-P3)") (class "Default")
      (node (ref "C14") (pin "1") (pinfunction "1_1") (pintype "passive"))
      (node (ref "C15") (pin "2") (pinfunction "2_2") (pintype "passive"))
      (node (ref "MOTOR") (pin "3") (pinfunction "P3_3") (pintype "passive"))
      (node (ref "U3") (pin "4") (pinfunction "OUT_4") (pintype "passive"))
      (node (ref "U3") (pin "8") (pinfunction "OUT_8") (pintype "passive"))
    )
    (net (code "48") (name "Net-(S2A-2)") (class "Default")
      (node (ref "S2") (pin "P1.2") (pinfunction "2_P1.2") (pintype "passive"))
      (node (ref "U4") (pin "7") (pinfunction "WP_7") (pintype "input"))
    )
    (net (code "49") (name "Net-(S2B-1)") (class "Default")
      (node (ref "R16") (pin "1") (pinfunction "1_1") (pintype "passive"))
      (node (ref "S2") (pin "P2.1") (pinfunction "1_P2.1") (pintype "passive"))
      (node (ref "U9") (pin "33") (pinfunction "PE2(~{HWB})_33") (pintype "bidirectional"))
    )
    (net (code "50") (name "Net-(U1-IN)") (class "Default")
      (node (ref "R3") (pin "2") (pinfunction "2_2") (pintype "passive"))
      (node (ref "U1") (pin "2") (pinfunction "IN_2") (pintype "input"))
    )
    (net (code "51") (name "Net-(U1-INH)") (class "Default")
      (node (ref "R1") (pin "2") (pinfunction "2_2") (pintype "passive"))
      (node (ref "U1") (pin "3") (pinfunction "INH_3") (pintype "input"))
    )
    (net (code "52") (name "Net-(U1-SR)") (class "Default")
      (node (ref "C1") (pin "1") (pinfunction "1_1") (pintype "passive"))
      (node (ref "R4") (pin "2") (pinfunction "2_2") (pintype "passive"))
      (node (ref "U1") (pin "5") (pinfunction "SR_5") (pintype "passive"))
    )
    (net (code "53") (name "Net-(U2-IN)") (class "Default")
      (node (ref "R7") (pin "2") (pinfunction "2_2") (pintype "passive"))
      (node (ref "U2") (pin "2") (pinfunction "IN_2") (pintype "input"))
    )
    (net (code "54") (name "Net-(U2-INH)") (class "Default")
      (node (ref "R5") (pin "2") (pinfunction "2_2") (pintype "passive"))
      (node (ref "U2") (pin "3") (pinfunction "INH_3") (pintype "input"))
    )
    (net (code "55") (name "Net-(U2-SR)") (class "Default")
      (node (ref "C6") (pin "1") (pinfunction "1_1") (pintype "passive"))
      (node (ref "R8") (pin "2") (pinfunction "2_2") (pintype "passive"))
      (node (ref "U2") (pin "5") (pinfunction "SR_5") (pintype "passive"))
    )
    (net (code "56") (name "Net-(U3-IN)") (class "Default")
      (node (ref "R11") (pin "2") (pinfunction "2_2") (pintype "passive"))
      (node (ref "U3") (pin "2") (pinfunction "IN_2") (pintype "input"))
    )
    (net (code "57") (name "Net-(U3-INH)") (class "Default")
      (node (ref "R9") (pin "2") (pinfunction "2_2") (pintype "passive"))
      (node (ref "U3") (pin "3") (pinfunction "INH_3") (pintype "input"))
    )
    (net (code "58") (name "Net-(U3-SR)") (class "Default")
      (node (ref "C10") (pin "1") (pinfunction "1_1") (pintype "passive"))
      (node (ref "R12") (pin "2") (pinfunction "2_2") (pintype "passive"))
      (node (ref "U3") (pin "5") (pinfunction "SR_5") (pintype "passive"))
    )
    (net (code "59") (name "Net-(U6A-B)") (class "Default")
      (node (ref "R37") (pin "2") (pinfunction "2_2") (pintype "passive"))
      (node (ref "U6") (pin "2") (pinfunction "B_2") (pintype "passive"))
      (node (ref "U6") (pin "5") (pinfunction "B_5") (pintype "passive"))
      (node (ref "U6") (pin "6") (pinfunction "C_6") (pintype "passive"))
    )
    (net (code "60") (name "Net-(U7-ADJ)") (class "Default")
      (node (ref "R36") (pin "2") (pinfunction "2_2") (pintype "passive"))
      (node (ref "U7") (pin "P5") (pinfunction "ADJ_P5") (pintype "passive"))
    )
    (net (code "61") (name "Net-(U8-G)") (class "Default")
      (node (ref "D1") (pin "A") (pinfunction "A_A") (pintype "passive"))
      (node (ref "R14") (pin "2") (pinfunction "2_2") (pintype "passive"))
      (node (ref "U8") (pin "1") (pinfunction "G_1") (pintype "passive"))
    )
    (net (code "62") (name "Net-(U9-AREF)") (class "Default")
      (node (ref "C20") (pin "1") (pinfunction "1_1") (pintype "passive"))
      (node (ref "U9") (pin "42") (pinfunction "AREF_42") (pintype "bidirectional"))
    )
    (net (code "63") (name "Net-(U9-D+)") (class "Default")
      (node (ref "R17") (pin "2") (pinfunction "2_2") (pintype "passive"))
      (node (ref "U9") (pin "4") (pinfunction "D+_4") (pintype "bidirectional"))
    )
    (net (code "64") (name "Net-(U9-D-)") (class "Default")
      (node (ref "R18") (pin "2") (pinfunction "2_2") (pintype "passive"))
      (node (ref "U9") (pin "3") (pinfunction "D-_3") (pintype "bidirectional"))
    )
    (net (code "65") (name "Net-(U9-UCAP)") (class "Default")
      (node (ref "C21") (pin "1") (pinfunction "1_1") (pintype "passive"))
      (node (ref "U9") (pin "6") (pinfunction "UCAP_6") (pintype "bidirectional"))
    )
    (net (code "66") (name "Net-(U9-XTAL1)") (class "Default")
      (node (ref "C19") (pin "1") (pinfunction "1_1") (pintype "passive"))
      (node (ref "R13") (pin "2") (pinfunction "2_2") (pintype "passive"))
      (node (ref "U9") (pin "17") (pinfunction "XTAL1_17") (pintype "bidirectional"))
      (node (ref "XTAL1") (pin "P1") (pinfunction "1_P1") (pintype "passive"))
    )
    (net (code "67") (name "Net-(U9-XTAL2)") (class "Default")
      (node (ref "C18") (pin "1") (pinfunction "1_1") (pintype "passive"))
      (node (ref "R13") (pin "1") (pinfunction "1_1") (pintype "passive"))
      (node (ref "U9") (pin "16") (pinfunction "XTAL2_16") (pintype "bidirectional"))
      (node (ref "XTAL1") (pin "P3") (pinfunction "3_P3") (pintype "passive"))
    )
    (net (code "68") (name "Net-(U11-G)") (class "Default")
      (node (ref "R38") (pin "2") (pinfunction "2_2") (pintype "passive"))
      (node (ref "U11") (pin "1") (pinfunction "G_1") (pintype "passive"))
      (node (ref "U6") (pin "3") (pinfunction "C_3") (pintype "passive"))
    )
    (net (code "69") (name "Net-(U12A-D)") (class "Default")
      (node (ref "LED1") (pin "B") (pinfunction "B_B") (pintype "passive"))
      (node (ref "U12") (pin "6") (pinfunction "D_6") (pintype "passive"))
    )
    (net (code "70") (name "Net-(U12B-D)") (class "Default")
      (node (ref "LED1") (pin "G") (pinfunction "G_G") (pintype "passive"))
      (node (ref "U12") (pin "3") (pinfunction "D_3") (pintype "passive"))
    )
    (net (code "71") (name "VPP") (class "Default")
      (node (ref "C11") (pin "1") (pinfunction "1_1") (pintype "passive"))
      (node (ref "C12") (pin "1") (pinfunction "1_1") (pintype "passive"))
      (node (ref "C13") (pin "1") (pinfunction "1_1") (pintype "passive"))
      (node (ref "C15") (pin "1") (pinfunction "1_1") (pintype "passive"))
      (node (ref "C16") (pin "+") (pinfunction "+_+") (pintype "passive"))
      (node (ref "C3") (pin "1") (pinfunction "1_1") (pintype "passive"))
      (node (ref "C40") (pin "1") (pinfunction "1_1") (pintype "passive"))
      (node (ref "C7") (pin "1") (pinfunction "1_1") (pintype "passive"))
      (node (ref "D1") (pin "C") (pinfunction "C_C") (pintype "passive"))
      (node (ref "D2") (pin "C") (pinfunction "C_C") (pintype "passive"))
      (node (ref "U1") (pin "7") (pinfunction "VS_7") (pintype "power_in"))
      (node (ref "U2") (pin "7") (pinfunction "VS_7") (pintype "power_in"))
      (node (ref "U3") (pin "7") (pinfunction "VS_7") (pintype "power_in"))
      (node (ref "U8") (pin "3") (pinfunction "S_3") (pintype "passive"))
    )
    (net (code "72") (name "unconnected-(J1-Pad7)") (class "Default")
      (node (ref "J1") (pin "7") (pinfunction "7_7") (pintype "passive"))
    )
    (net (code "73") (name "unconnected-(J1-Pad8)") (class "Default")
      (node (ref "J1") (pin "8") (pinfunction "8_8") (pintype "passive"))
    )
    (net (code "74") (name "unconnected-(J1-Pad10)") (class "Default")
      (node (ref "J1") (pin "10") (pinfunction "10_10") (pintype "passive"))
    )
    (net (code "75") (name "unconnected-(J1-Pad11)") (class "Default")
      (node (ref "J1") (pin "11") (pinfunction "11_11") (pintype "passive"))
    )
    (net (code "76") (name "unconnected-(J1-Pad13)") (class "Default")
      (node (ref "J1") (pin "13") (pinfunction "13_13") (pintype "passive"))
    )
    (net (code "77") (name "unconnected-(J1-Pad15)") (class "Default")
      (node (ref "J1") (pin "15") (pinfunction "15_15") (pintype "passive"))
    )
    (net (code "78") (name "unconnected-(J1-Pad16)") (class "Default")
      (node (ref "J1") (pin "16") (pinfunction "16_16") (pintype "passive"))
    )
    (net (code "79") (name "unconnected-(J1-Pad18)") (class "Default")
      (node (ref "J1") (pin "18") (pinfunction "18_18") (pintype "passive"))
    )
    (net (code "80") (name "unconnected-(J1-Pad22)") (class "Default")
      (node (ref "J1") (pin "22") (pinfunction "22_22") (pintype "passive"))
    )
    (net (code "81") (name "unconnected-(J1-Pad24)") (class "Default")
      (node (ref "J1") (pin "24") (pinfunction "24_24") (pintype "passive"))
    )
    (net (code "82") (name "unconnected-(J1-Pad26)") (class "Default")
      (node (ref "J1") (pin "26") (pinfunction "26_26") (pintype "passive"))
    )
    (net (code "83") (name "unconnected-(J1-Pad29)") (class "Default")
      (node (ref "J1") (pin "29") (pinfunction "29_29") (pintype "passive"))
    )
    (net (code "84") (name "unconnected-(J1-Pad31)") (class "Default")
      (node (ref "J1") (pin "31") (pinfunction "31_31") (pintype "passive"))
    )
    (net (code "85") (name "unconnected-(J1-Pad32)") (class "Default")
      (node (ref "J1") (pin "32") (pinfunction "32_32") (pintype "passive"))
    )
    (net (code "86") (name "unconnected-(J1-Pad33)") (class "Default")
      (node (ref "J1") (pin "33") (pinfunction "33_33") (pintype "passive"))
    )
    (net (code "87") (name "unconnected-(J1-Pad35)") (class "Default")
      (node (ref "J1") (pin "35") (pinfunction "35_35") (pintype "passive"))
    )
    (net (code "88") (name "unconnected-(J1-Pad36)") (class "Default")
      (node (ref "J1") (pin "36") (pinfunction "36_36") (pintype "passive"))
    )
    (net (code "89") (name "unconnected-(J1-Pad37)") (class "Default")
      (node (ref "J1") (pin "37") (pinfunction "37_37") (pintype "passive"))
    )
    (net (code "90") (name "unconnected-(J1-Pad38)") (class "Default")
      (node (ref "J1") (pin "38") (pinfunction "38_38") (pintype "passive"))
    )
    (net (code "91") (name "unconnected-(J1-Pad40)") (class "Default")
      (node (ref "J1") (pin "40") (pinfunction "40_40") (pintype "passive"))
    )
    (net (code "92") (name "unconnected-(J2-ID-Pad4)") (class "Default")
      (node (ref "J2") (pin "4") (pinfunction "ID_4") (pintype "bidirectional"))
    )
    (net (code "93") (name "unconnected-(U5-NC-Pad6)") (class "Default")
      (node (ref "U5") (pin "6") (pinfunction "NC_6") (pintype "no_connect"))
    )
    (net (code "94") (name "unconnected-(U5-NC-Pad9)") (class "Default")
      (node (ref "U5") (pin "9") (pinfunction "NC_9") (pintype "no_connect"))
    )
    (net (code "95") (name "unconnected-(U7-INH-PadP1)") (class "Default")
      (node (ref "U7") (pin "P1") (pinfunction "INH_P1") (pintype "open_collector"))
    )
    (net (code "96") (name "unconnected-(U9-PD5(XCK{slash}CTS)-Pad22)") (class "Default")
      (node (ref "U9") (pin "22") (pinfunction "PD5(XCK/CTS)_22") (pintype "bidirectional"))
    )
  )
)
